# Output.net
KiCad netlist of a schematic drawn in Altium Designer
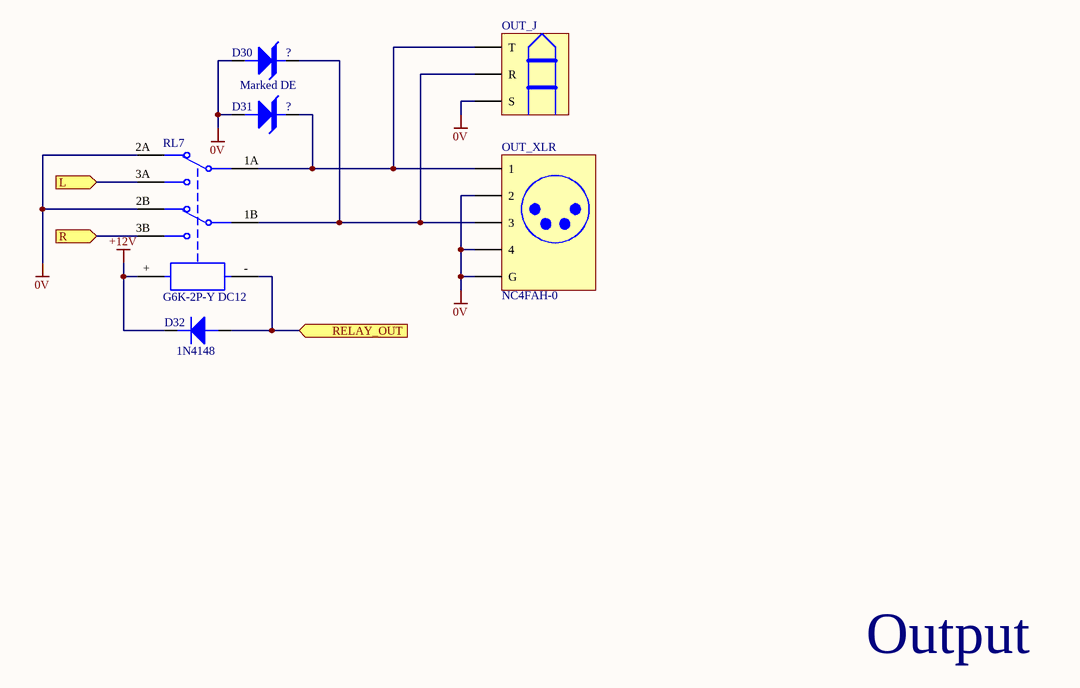
[diagram p0: Output.SchDoc]

(export (version "E")
  (design (tool "Eeschema 10.0.6"))
  (components
    (comp (ref "D30")
      (value "?")
      (footprint "DIOM4336X24N")
      (description "Generic TVS diode")
      (fields (field (name "MANUFACTURER") "Bourns") (field (name "MANUFACTURER PART NUMBER") "SMBJ30A"))
      (libsource (lib "Topping_L50") (part "TVS"))
    )
    (comp (ref "D31")
      (value "?")
      (footprint "DIOM4336X24N")
      (description "Generic TVS diode")
      (fields (field (name "MANUFACTURER") "Bourns") (field (name "MANUFACTURER PART NUMBER") "SMBJ30A"))
      (libsource (lib "Topping_L50") (part "TVS"))
    )
    (comp (ref "D32")
      (value "1N4148")
      (description "Generic small signal diode")
      (fields (field (name "MANUFACTURER") "Generic") (field (name "MANUFACTURER PART NUMBER") "BAT48ZFILM"))
      (libsource (lib "Topping_L50") (part "1N4148"))
    )
    (comp (ref "OUT_J")
      (value "SJ-63053A")
      (footprint "SJ-63053A")
      (fields (field (name "MANUFACTURER") "Same Sky"))
      (libsource (lib "Topping_L50") (part "SJ-63053A"))
    )
    (comp (ref "OUT_XLR")
      (value "NC4FAH-0")
      (description "4 pole XLR female receptacle with 1/4\" stereo jack, horizontal PCB mount")
      (fields (field (name "MANUFACTURER") "Neutrik"))
      (libsource (lib "Topping_L50") (part "NC4FAH-0"))
    )
    (comp (ref "RL7")
      (value "G6K-2P-Y DC12")
      (footprint "G6K-2P-Y")
      (description "Low Signal Relays - PCB Gullwing NoLatch 3.2 DPDT 12VDC 100mW T/R")
      (fields (field (name "MANUFACTURER") "Omron"))
      (libsource (lib "Topping_L50") (part "G6K-2P-Y DC12"))
    )
  )
  (nets
    (net (code "1") (name "+12V") (class "Default")
      (node (ref "D32") (pin "K") (pinfunction "K_K") (pintype "passive"))
      (node (ref "RL7") (pin "+") (pinfunction "+_+") (pintype "passive"))
    )
    (net (code "2") (name "/L") (class "Default")
      (node (ref "RL7") (pin "3A") (pinfunction "3A_3A") (pintype "passive"))
    )
    (net (code "3") (name "/R") (class "Default")
      (node (ref "RL7") (pin "3B") (pinfunction "3B_3B") (pintype "passive"))
    )
    (net (code "4") (name "/RELAY_OUT") (class "Default")
      (node (ref "D32") (pin "A") (pinfunction "A_A") (pintype "passive"))
      (node (ref "RL7") (pin "-") (pinfunction "-_-") (pintype "passive"))
    )
    (net (code "5") (name "0V") (class "Default")
      (node (ref "D30") (pin "A") (pinfunction "A_A") (pintype "passive"))
      (node (ref "D31") (pin "A") (pinfunction "A_A") (pintype "passive"))
      (node (ref "OUT_J") (pin "S") (pinfunction "S_S") (pintype "passive"))
      (node (ref "OUT_XLR") (pin "2") (pinfunction "2_2") (pintype "passive"))
      (node (ref "OUT_XLR") (pin "4") (pinfunction "4_4") (pintype "passive"))
      (node (ref "OUT_XLR") (pin "G") (pinfunction "G_G") (pintype "passive"))
      (node (ref "RL7") (pin "2A") (pinfunction "2A_2A") (pintype "passive"))
      (node (ref "RL7") (pin "2B") (pinfunction "2B_2B") (pintype "passive"))
    )
    (net (code "6") (name "Net-(D30-PadK)") (class "Default")
      (node (ref "D30") (pin "K") (pinfunction "K_K") (pintype "passive"))
      (node (ref "OUT_J") (pin "R") (pinfunction "R_R") (pintype "passive"))
      (node (ref "OUT_XLR") (pin "3") (pinfunction "3_3") (pintype "passive"))
      (node (ref "RL7") (pin "1B") (pinfunction "1B_1B") (pintype "passive"))
    )
    (net (code "7") (name "Net-(D31-PadK)") (class "Default")
      (node (ref "D31") (pin "K") (pinfunction "K_K") (pintype "passive"))
      (node (ref "OUT_J") (pin "T") (pinfunction "T_T") (pintype "passive"))
      (node (ref "OUT_XLR") (pin "1") (pinfunction "1_1") (pintype "passive"))
      (node (ref "RL7") (pin "1A") (pinfunction "1A_1A") (pintype "passive"))
    )
  )
)
